# Main.net
KiCad netlist of a schematic drawn in Altium Designer
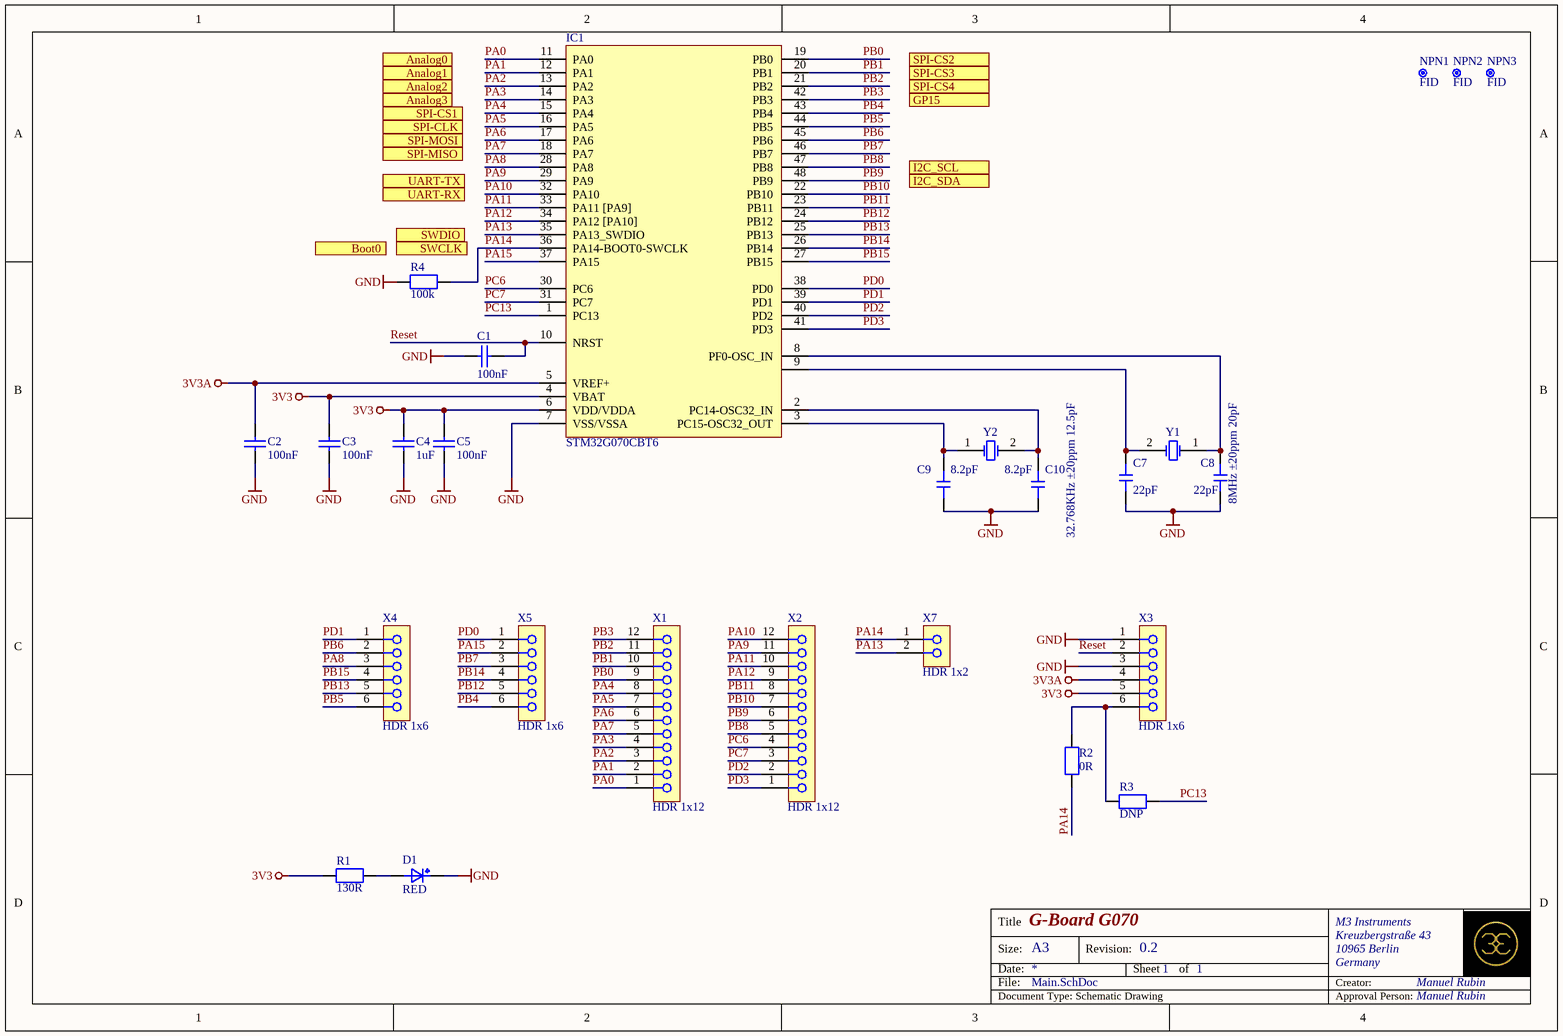
[diagram p0: Main.SchDoc]

(export (version "E")
  (design (tool "Eeschema 10.0.6"))
  (components
    (comp (ref "C1")
      (value "100nF")
      (footprint "CAPC1005X55")
      (description "X7R 100nF ±10% 16V 0402 Multilayer Ceramic Capacitors MLCC - SMD/SMT ROHS")
      (fields
        (field (name "MANUFACTURER") "Samsung Electro-Mechanics")
        (field (name "MANUFACTURER PART NUMBER") "CL05B104KO5NNNC")
      )
      (libsource (lib "Caps") (part "CAP_100nF_0402"))
    )
    (comp (ref "C2")
      (value "100nF")
      (footprint "CAPC1005X55")
      (description "X7R 100nF ±10% 16V 0402 Multilayer Ceramic Capacitors MLCC - SMD/SMT ROHS")
      (fields
        (field (name "MANUFACTURER") "Samsung Electro-Mechanics")
        (field (name "MANUFACTURER PART NUMBER") "CL05B104KO5NNNC")
      )
      (libsource (lib "Caps") (part "CAP_100nF_0402"))
    )
    (comp (ref "C3")
      (value "100nF")
      (footprint "CAPC1005X55")
      (description "X7R 100nF ±10% 16V 0402 Multilayer Ceramic Capacitors MLCC - SMD/SMT ROHS")
      (fields
        (field (name "MANUFACTURER") "Samsung Electro-Mechanics")
        (field (name "MANUFACTURER PART NUMBER") "CL05B104KO5NNNC")
      )
      (libsource (lib "Caps") (part "CAP_100nF_0402"))
    )
    (comp (ref "C4")
      (value "1uF")
      (footprint "CAPC1005X55")
      (description "X5R 25V ±10% 1uF 0402 Multilayer Ceramic Capacitors MLCC - SMD/SMT ROHS")
      (fields
        (field (name "MANUFACTURER") "Samsung Electro-Mechanics")
        (field (name "MANUFACTURER PART NUMBER") "CL05A105KA5NQNC")
      )
      (libsource (lib "Caps") (part "CAP_1uF_0402"))
    )
    (comp (ref "C5")
      (value "100nF")
      (footprint "CAPC1005X55")
      (description "X7R 100nF ±10% 16V 0402 Multilayer Ceramic Capacitors MLCC - SMD/SMT ROHS")
      (fields
        (field (name "MANUFACTURER") "Samsung Electro-Mechanics")
        (field (name "MANUFACTURER PART NUMBER") "CL05B104KO5NNNC")
      )
      (libsource (lib "Caps") (part "CAP_100nF_0402"))
    )
    (comp (ref "C7")
      (value "22pF")
      (footprint "CAPC1608X95N")
      (description "Chip capacitors")
      (fields
        (field (name "MANUFACTURER") "Samsung Electro-Mechanics")
        (field (name "MANUFACTURER PART NUMBER") "CL10C220JB8NNNC")
      )
      (libsource (lib "Caps") (part "CAP_22pF_50V_0603"))
    )
    (comp (ref "C8")
      (value "22pF")
      (footprint "CAPC1608X95N")
      (description "Chip capacitors")
      (fields
        (field (name "MANUFACTURER") "Samsung Electro-Mechanics")
        (field (name "MANUFACTURER PART NUMBER") "CL10C220JB8NNNC")
      )
      (libsource (lib "Caps") (part "CAP_22pF_50V_0603"))
    )
    (comp (ref "C9")
      (value "8.2pF")
      (footprint "CAPC1608X95N")
      (description "Multilayer Ceramic Capacitors MLCC - SMD/SMT 0402 8.0pF 50volts C0G +/-0.5pF")
      (fields
        (field (name "MANUFACTURER") "Guangdong Fenghua Advanced Tech")
        (field (name "MANUFACTURER PART NUMBER") "0603CG8R2C500NT")
      )
      (libsource (lib "Caps") (part "CAP_8p2_50V_0603"))
    )
    (comp (ref "C10")
      (value "8.2pF")
      (footprint "CAPC1608X95N")
      (description "Multilayer Ceramic Capacitors MLCC - SMD/SMT 0402 8.0pF 50volts C0G +/-0.5pF")
      (fields
        (field (name "MANUFACTURER") "Guangdong Fenghua Advanced Tech")
        (field (name "MANUFACTURER PART NUMBER") "0603CG8R2C500NT")
      )
      (libsource (lib "Caps") (part "CAP_8p2_50V_0603"))
    )
    (comp (ref "D1")
      (value "RED")
      (footprint "WL-SMCW_0805")
      (description "Standard LEDs - SMD WL-SMCW SMDMono TpVw Waterclr 0805 Red")
      (fields
        (field (name "MANUFACTURER") "Wurth Elektronik")
        (field (name "MANUFACTURER PART NUMBER") "150080RS75000")
      )
      (libsource (lib "Diodes") (part "LED_0805_RED_AK"))
    )
    (comp (ref "IC1")
      (value "STM32G070CBT6")
      (footprint "LQFP-48_7x7x05P")
      (fields (field (name "MANUFACTURER") "STMicroelectronics"))
      (libsource (lib "ICs") (part "STM32G070CBT6"))
    )
    (comp (ref "NPN1")
      (value "FID")
      (footprint "Fiducial_1mm")
      (libsource (lib "MISC") (part "Fiducial_1mm"))
    )
    (comp (ref "NPN2")
      (value "FID")
      (footprint "Fiducial_1mm")
      (libsource (lib "MISC") (part "Fiducial_1mm"))
    )
    (comp (ref "NPN3")
      (value "FID")
      (footprint "Fiducial_1mm")
      (libsource (lib "MISC") (part "Fiducial_1mm"))
    )
    (comp (ref "R1")
      (value "130R")
      (footprint "RESC2012X70N")
      (description "Dickfilmwiderstände - SMD 1/8watt 130ohms 1% 100ppm")
      (fields
        (field (name "MANUFACTURER") "Vishay / Dale")
        (field (name "MANUFACTURER PART NUMBER") "CRCW0805130RFKEA")
      )
      (libsource (lib "Resistors") (part "RES_130R_0805"))
    )
    (comp (ref "R2")
      (value "0R")
      (footprint "RESC1608X55N")
      (description "Thick Film Resistors - SMD 1/10watt ZEROohm Jumper")
      (fields
        (field (name "MANUFACTURER") "Vishay")
        (field (name "MANUFACTURER PART NUMBER") "CRCW06030000Z0EA")
      )
      (libsource (lib "Resistors") (part "RES_0R_0603"))
    )
    (comp (ref "R3")
      (value "DNP")
      (footprint "RESC1608X55N")
      (description "Resistor SMD 0603 - not populated")
      (libsource (lib "Resistors") (part "RES_DNF_0603"))
    )
    (comp (ref "R4")
      (value "100k")
      (footprint "RESC1005X40N")
      (description "Thick Film Resistors - SMD 63mW 100Kohms 1%")
      (fields
        (field (name "MANUFACTURER") "Vishay")
        (field (name "MANUFACTURER PART NUMBER") "RC0402FR-07100KL")
      )
      (libsource (lib "Gfs_Library") (part "RES_100k_0402"))
    )
    (comp (ref "X1")
      (value "HDR 1x12")
      (footprint "61301211121_no")
      (description "Board-to-Board-Steckverbinder, 2.54 mm, 12 Kontakt(e), Stiftleiste 1-Reihig")
      (fields (field (name "MANUFACTURER") "WE") (field (name "MANUFACTURER PART NUMBER") "61301211121"))
      (libsource (lib "Connectors") (part "CON_HEADER_1X12_no_overlay"))
    )
    (comp (ref "X2")
      (value "HDR 1x12")
      (footprint "61301211121_no")
      (description "Board-to-Board-Steckverbinder, 2.54 mm, 12 Kontakt(e), Stiftleiste 1-Reihig")
      (fields (field (name "MANUFACTURER") "WE") (field (name "MANUFACTURER PART NUMBER") "61301211121"))
      (libsource (lib "Connectors") (part "CON_HEADER_1X12_no_overlay"))
    )
    (comp (ref "X3")
      (value "HDR 1x6")
      (footprint "61300611121_no")
      (description "Board-to-Board-Steckverbinder, 2.54 mm, 6 Kontakt(e), Stiftleiste 1-Reihig")
      (fields (field (name "MANUFACTURER") "WE") (field (name "MANUFACTURER PART NUMBER") "61300611121"))
      (libsource (lib "Connectors") (part "CON_HEADER_1X6_no_overlay"))
    )
    (comp (ref "X4")
      (value "HDR 1x6")
      (footprint "61300611121_no")
      (description "Board-to-Board-Steckverbinder, 2.54 mm, 6 Kontakt(e), Stiftleiste 1-Reihig")
      (fields (field (name "MANUFACTURER") "WE") (field (name "MANUFACTURER PART NUMBER") "61300611121"))
      (libsource (lib "Connectors") (part "CON_HEADER_1X6_no_overlay"))
    )
    (comp (ref "X5")
      (value "HDR 1x6")
      (footprint "61300611121_no")
      (description "Board-to-Board-Steckverbinder, 2.54 mm, 6 Kontakt(e), Stiftleiste 1-Reihig")
      (fields (field (name "MANUFACTURER") "WE") (field (name "MANUFACTURER PART NUMBER") "61300611121"))
      (libsource (lib "Connectors") (part "CON_HEADER_1X6_no_overlay"))
    )
    (comp (ref "X7")
      (value "HDR 1x2")
      (footprint "CON_HEADER2.54_1x2W_no")
      (description "Board-to-Board-Steckverbinder, 2.54 mm, 2 Kontakt(e), Stiftleiste 1-Reihig")
      (fields
        (field (name "MANUFACTURER") "Samtec")
        (field (name "MANUFACTURER PART NUMBER") "TSW-102-07-T-S")
      )
      (libsource (lib "Connectors") (part "CON_HEADER_1X2_no_overlay"))
    )
    (comp (ref "Y1")
      (value "8MHz ±20ppm 20pF")
      (footprint "SMD-5032_2P")
      (description "8MHz SMD Crystal Resonator 20pF ±10ppm ±50ppm -40℃~+85℃ SMD5032-2P Crystals ROHS")
      (fields
        (field (name "MANUFACTURER") "Yangxing Tech")
        (field (name "MANUFACTURER PART NUMBER") "X50328MSB2GI")
      )
      (libsource (lib "MISC") (part "SMD-5032_2P 8MHz 20ppm 20pF"))
    )
    (comp (ref "Y2")
      (value "32.768KHz ±20ppm 12.5pF")
      (footprint "SMD-3215_2P FC - 135")
      (description "32.768kHz SMD Crystal Resonator 12.5pF 70kΩ ±20ppm -40℃~+85℃ SMD3215-2P Crystals ROHS")
      (fields
        (field (name "MANUFACTURER") "Seiko Epson")
        (field (name "MANUFACTURER PART NUMBER") "Q13FC1350000400")
      )
      (libsource (lib "MISC") (part "SMD-3215_2P 32.768KHz 20ppm 12.5pF"))
    )
  )
  (nets
    (net (code "9") (name "/PA0") (class "Default")
      (node (ref "IC1") (pin "11") (pinfunction "PA0_11") (pintype "passive"))
      (node (ref "X1") (pin "1") (pinfunction "1_1") (pintype "passive"))
    )
    (net (code "10") (name "/PA1") (class "Default")
      (node (ref "IC1") (pin "12") (pinfunction "PA1_12") (pintype "passive"))
      (node (ref "X1") (pin "2") (pinfunction "2_2") (pintype "passive"))
    )
    (net (code "11") (name "/PA2") (class "Default")
      (node (ref "IC1") (pin "13") (pinfunction "PA2_13") (pintype "passive"))
      (node (ref "X1") (pin "3") (pinfunction "3_3") (pintype "passive"))
    )
    (net (code "12") (name "/PA3") (class "Default")
      (node (ref "IC1") (pin "14") (pinfunction "PA3_14") (pintype "passive"))
      (node (ref "X1") (pin "4") (pinfunction "4_4") (pintype "passive"))
    )
    (net (code "13") (name "/PA4") (class "Default")
      (node (ref "IC1") (pin "15") (pinfunction "PA4_15") (pintype "passive"))
      (node (ref "X1") (pin "8") (pinfunction "8_8") (pintype "passive"))
    )
    (net (code "14") (name "/PA5") (class "Default")
      (node (ref "IC1") (pin "16") (pinfunction "PA5_16") (pintype "passive"))
      (node (ref "X1") (pin "7") (pinfunction "7_7") (pintype "passive"))
    )
    (net (code "15") (name "/PA6") (class "Default")
      (node (ref "IC1") (pin "17") (pinfunction "PA6_17") (pintype "passive"))
      (node (ref "X1") (pin "6") (pinfunction "6_6") (pintype "passive"))
    )
    (net (code "16") (name "/PA7") (class "Default")
      (node (ref "IC1") (pin "18") (pinfunction "PA7_18") (pintype "passive"))
      (node (ref "X1") (pin "5") (pinfunction "5_5") (pintype "passive"))
    )
    (net (code "17") (name "/PA8") (class "Default")
      (node (ref "IC1") (pin "28") (pinfunction "PA8_28") (pintype "passive"))
      (node (ref "X4") (pin "3") (pinfunction "3_3") (pintype "passive"))
    )
    (net (code "18") (name "/PA9") (class "Default")
      (node (ref "IC1") (pin "29") (pinfunction "PA9_29") (pintype "passive"))
      (node (ref "X2") (pin "11") (pinfunction "11_11") (pintype "passive"))
    )
    (net (code "19") (name "/PA10") (class "Default")
      (node (ref "IC1") (pin "32") (pinfunction "PA10_32") (pintype "passive"))
      (node (ref "X2") (pin "12") (pinfunction "12_12") (pintype "passive"))
    )
    (net (code "20") (name "/PA11") (class "Default")
      (node (ref "IC1") (pin "33") (pinfunction "PA11_[PA9]_33") (pintype "passive"))
      (node (ref "X2") (pin "10") (pinfunction "10_10") (pintype "passive"))
    )
    (net (code "21") (name "/PA12") (class "Default")
      (node (ref "IC1") (pin "34") (pinfunction "PA12_[PA10]_34") (pintype "passive"))
      (node (ref "X2") (pin "9") (pinfunction "9_9") (pintype "passive"))
    )
    (net (code "22") (name "/PA13") (class "Default")
      (node (ref "IC1") (pin "35") (pinfunction "PA13_SWDIO_35") (pintype "power_in"))
      (node (ref "X7") (pin "2") (pinfunction "2_2") (pintype "passive"))
    )
    (net (code "23") (name "/PA14") (class "Default")
      (node (ref "IC1") (pin "36") (pinfunction "PA14-BOOT0-SWCLK_36") (pintype "power_in"))
      (node (ref "R2") (pin "1") (pinfunction "1_1") (pintype "passive"))
      (node (ref "R4") (pin "1") (pinfunction "1_1") (pintype "passive"))
      (node (ref "X7") (pin "1") (pinfunction "1_1") (pintype "passive"))
    )
    (net (code "24") (name "/PA15") (class "Default")
      (node (ref "IC1") (pin "37") (pinfunction "PA15_37") (pintype "passive"))
      (node (ref "X5") (pin "2") (pinfunction "2_2") (pintype "passive"))
    )
    (net (code "25") (name "/PB0") (class "Default")
      (node (ref "IC1") (pin "19") (pinfunction "PB0_19") (pintype "passive"))
      (node (ref "X1") (pin "9") (pinfunction "9_9") (pintype "passive"))
    )
    (net (code "26") (name "/PB1") (class "Default")
      (node (ref "IC1") (pin "20") (pinfunction "PB1_20") (pintype "passive"))
      (node (ref "X1") (pin "10") (pinfunction "10_10") (pintype "passive"))
    )
    (net (code "27") (name "/PB2") (class "Default")
      (node (ref "IC1") (pin "21") (pinfunction "PB2_21") (pintype "passive"))
      (node (ref "X1") (pin "11") (pinfunction "11_11") (pintype "passive"))
    )
    (net (code "28") (name "/PB3") (class "Default")
      (node (ref "IC1") (pin "42") (pinfunction "PB3_42") (pintype "passive"))
      (node (ref "X1") (pin "12") (pinfunction "12_12") (pintype "passive"))
    )
    (net (code "29") (name "/PB4") (class "Default")
      (node (ref "IC1") (pin "43") (pinfunction "PB4_43") (pintype "passive"))
      (node (ref "X5") (pin "6") (pinfunction "6_6") (pintype "passive"))
    )
    (net (code "30") (name "/PB5") (class "Default")
      (node (ref "IC1") (pin "44") (pinfunction "PB5_44") (pintype "passive"))
      (node (ref "X4") (pin "6") (pinfunction "6_6") (pintype "passive"))
    )
    (net (code "31") (name "/PB6") (class "Default")
      (node (ref "IC1") (pin "45") (pinfunction "PB6_45") (pintype "passive"))
      (node (ref "X4") (pin "2") (pinfunction "2_2") (pintype "passive"))
    )
    (net (code "32") (name "/PB7") (class "Default")
      (node (ref "IC1") (pin "46") (pinfunction "PB7_46") (pintype "passive"))
      (node (ref "X5") (pin "3") (pinfunction "3_3") (pintype "passive"))
    )
    (net (code "33") (name "/PB8") (class "Default")
      (node (ref "IC1") (pin "47") (pinfunction "PB8_47") (pintype "power_in"))
      (node (ref "X2") (pin "5") (pinfunction "5_5") (pintype "passive"))
    )
    (net (code "34") (name "/PB9") (class "Default")
      (node (ref "IC1") (pin "48") (pinfunction "PB9_48") (pintype "power_in"))
      (node (ref "X2") (pin "6") (pinfunction "6_6") (pintype "passive"))
    )
    (net (code "35") (name "/PB10") (class "Default")
      (node (ref "IC1") (pin "22") (pinfunction "PB10_22") (pintype "passive"))
      (node (ref "X2") (pin "7") (pinfunction "7_7") (pintype "passive"))
    )
    (net (code "36") (name "/PB11") (class "Default")
      (node (ref "IC1") (pin "23") (pinfunction "PB11_23") (pintype "power_in"))
      (node (ref "X2") (pin "8") (pinfunction "8_8") (pintype "passive"))
    )
    (net (code "37") (name "/PB12") (class "Default")
      (node (ref "IC1") (pin "24") (pinfunction "PB12_24") (pintype "power_in"))
      (node (ref "X5") (pin "5") (pinfunction "5_5") (pintype "passive"))
    )
    (net (code "38") (name "/PB13") (class "Default")
      (node (ref "IC1") (pin "25") (pinfunction "PB13_25") (pintype "passive"))
      (node (ref "X4") (pin "5") (pinfunction "5_5") (pintype "passive"))
    )
    (net (code "39") (name "/PB14") (class "Default")
      (node (ref "IC1") (pin "26") (pinfunction "PB14_26") (pintype "passive"))
      (node (ref "X5") (pin "4") (pinfunction "4_4") (pintype "passive"))
    )
    (net (code "40") (name "/PB15") (class "Default")
      (node (ref "IC1") (pin "27") (pinfunction "PB15_27") (pintype "passive"))
      (node (ref "X4") (pin "4") (pinfunction "4_4") (pintype "passive"))
    )
    (net (code "41") (name "/PC6") (class "Default")
      (node (ref "IC1") (pin "30") (pinfunction "PC6_30") (pintype "passive"))
      (node (ref "X2") (pin "4") (pinfunction "4_4") (pintype "passive"))
    )
    (net (code "42") (name "/PC7") (class "Default")
      (node (ref "IC1") (pin "31") (pinfunction "PC7_31") (pintype "passive"))
      (node (ref "X2") (pin "3") (pinfunction "3_3") (pintype "passive"))
    )
    (net (code "43") (name "/PC13") (class "Default")
      (node (ref "IC1") (pin "1") (pinfunction "PC13_1") (pintype "power_in"))
      (node (ref "R3") (pin "2") (pinfunction "2_2") (pintype "passive"))
    )
    (net (code "44") (name "/PD0") (class "Default")
      (node (ref "IC1") (pin "38") (pinfunction "PD0_38") (pintype "passive"))
      (node (ref "X5") (pin "1") (pinfunction "1_1") (pintype "passive"))
    )
    (net (code "45") (name "/PD1") (class "Default")
      (node (ref "IC1") (pin "39") (pinfunction "PD1_39") (pintype "passive"))
      (node (ref "X4") (pin "1") (pinfunction "1_1") (pintype "passive"))
    )
    (net (code "46") (name "/PD2") (class "Default")
      (node (ref "IC1") (pin "40") (pinfunction "PD2_40") (pintype "passive"))
      (node (ref "X2") (pin "2") (pinfunction "2_2") (pintype "passive"))
    )
    (net (code "47") (name "/PD3") (class "Default")
      (node (ref "IC1") (pin "41") (pinfunction "PD3_41") (pintype "passive"))
      (node (ref "X2") (pin "1") (pinfunction "1_1") (pintype "passive"))
    )
    (net (code "48") (name "/Reset") (class "Default")
      (node (ref "C1") (pin "1") (pinfunction "1_1") (pintype "passive"))
      (node (ref "IC1") (pin "10") (pinfunction "NRST_10") (pintype "passive"))
      (node (ref "X3") (pin "2") (pinfunction "2_2") (pintype "passive"))
    )
    (net (code "60") (name "3V3") (class "Default")
      (node (ref "C3") (pin "2") (pinfunction "2_2") (pintype "passive"))
      (node (ref "C4") (pin "2") (pinfunction "2_2") (pintype "passive"))
      (node (ref "C5") (pin "2") (pinfunction "2_2") (pintype "passive"))
      (node (ref "IC1") (pin "4") (pinfunction "VBAT_4") (pintype "passive"))
      (node (ref "IC1") (pin "6") (pinfunction "VDD/VDDA_6") (pintype "passive"))
      (node (ref "R1") (pin "1") (pinfunction "1_1") (pintype "passive"))
      (node (ref "X3") (pin "5") (pinfunction "5_5") (pintype "passive"))
    )
    (net (code "61") (name "3V3A") (class "Default")
      (node (ref "C2") (pin "2") (pinfunction "2_2") (pintype "passive"))
      (node (ref "IC1") (pin "5") (pinfunction "VREF+_5") (pintype "passive"))
      (node (ref "X3") (pin "4") (pinfunction "4_4") (pintype "passive"))
    )
    (net (code "62") (name "GND") (class "Default")
      (node (ref "C1") (pin "2") (pinfunction "2_2") (pintype "passive"))
      (node (ref "C10") (pin "1") (pinfunction "1_1") (pintype "passive"))
      (node (ref "C2") (pin "1") (pinfunction "1_1") (pintype "passive"))
      (node (ref "C3") (pin "1") (pinfunction "1_1") (pintype "passive"))
      (node (ref "C4") (pin "1") (pinfunction "1_1") (pintype "passive"))
      (node (ref "C5") (pin "1") (pinfunction "1_1") (pintype "passive"))
      (node (ref "C7") (pin "2") (pinfunction "2_2") (pintype "passive"))
      (node (ref "C8") (pin "2") (pinfunction "2_2") (pintype "passive"))
      (node (ref "C9") (pin "1") (pinfunction "1_1") (pintype "passive"))
      (node (ref "D1") (pin "K") (pinfunction "K_K") (pintype "passive"))
      (node (ref "IC1") (pin "7") (pinfunction "VSS/VSSA_7") (pintype "passive"))
      (node (ref "R4") (pin "2") (pinfunction "2_2") (pintype "passive"))
      (node (ref "X3") (pin "1") (pinfunction "1_1") (pintype "passive"))
      (node (ref "X3") (pin "3") (pinfunction "3_3") (pintype "passive"))
    )
    (net (code "63") (name "Net-(D1-PadA)") (class "Default")
      (node (ref "D1") (pin "A") (pinfunction "A_A") (pintype "passive"))
      (node (ref "R1") (pin "2") (pinfunction "2_2") (pintype "passive"))
    )
    (net (code "64") (name "Net-(IC1-PC14-OSC32_IN)") (class "Default")
      (node (ref "C10") (pin "2") (pinfunction "2_2") (pintype "passive"))
      (node (ref "IC1") (pin "2") (pinfunction "PC14-OSC32_IN_2") (pintype "passive"))
      (node (ref "Y2") (pin "2") (pinfunction "OSC2_2") (pintype "passive"))
    )
    (net (code "65") (name "Net-(IC1-PC15-OSC32_OUT)") (class "Default")
      (node (ref "C9") (pin "2") (pinfunction "2_2") (pintype "passive"))
      (node (ref "IC1") (pin "3") (pinfunction "PC15-OSC32_OUT_3") (pintype "passive"))
      (node (ref "Y2") (pin "1") (pinfunction "OSC1_1") (pintype "passive"))
    )
    (net (code "66") (name "Net-(IC1-PF0-OSC_IN)") (class "Default")
      (node (ref "C8") (pin "1") (pinfunction "1_1") (pintype "passive"))
      (node (ref "IC1") (pin "8") (pinfunction "PF0-OSC_IN_8") (pintype "power_in"))
      (node (ref "Y1") (pin "1") (pinfunction "OSC1_1") (pintype "passive"))
    )
    (net (code "67") (name "Net-(IC1-PF1-OSC_OU'T)") (class "Default")
      (node (ref "C7") (pin "1") (pinfunction "1_1") (pintype "passive"))
      (node (ref "IC1") (pin "9") (pinfunction "PF1-OSC_OU'T_9") (pintype "power_in"))
      (node (ref "Y1") (pin "2") (pinfunction "OSC2_2") (pintype "passive"))
    )
    (net (code "68") (name "Net-(R2-Pad2)") (class "Default")
      (node (ref "R2") (pin "2") (pinfunction "2_2") (pintype "passive"))
      (node (ref "R3") (pin "1") (pinfunction "1_1") (pintype "passive"))
      (node (ref "X3") (pin "6") (pinfunction "6_6") (pintype "passive"))
    )
  )
)
